# PH_074_isolated_SMD_rev1_2.net
KiCad netlist of a schematic drawn in EAGLE
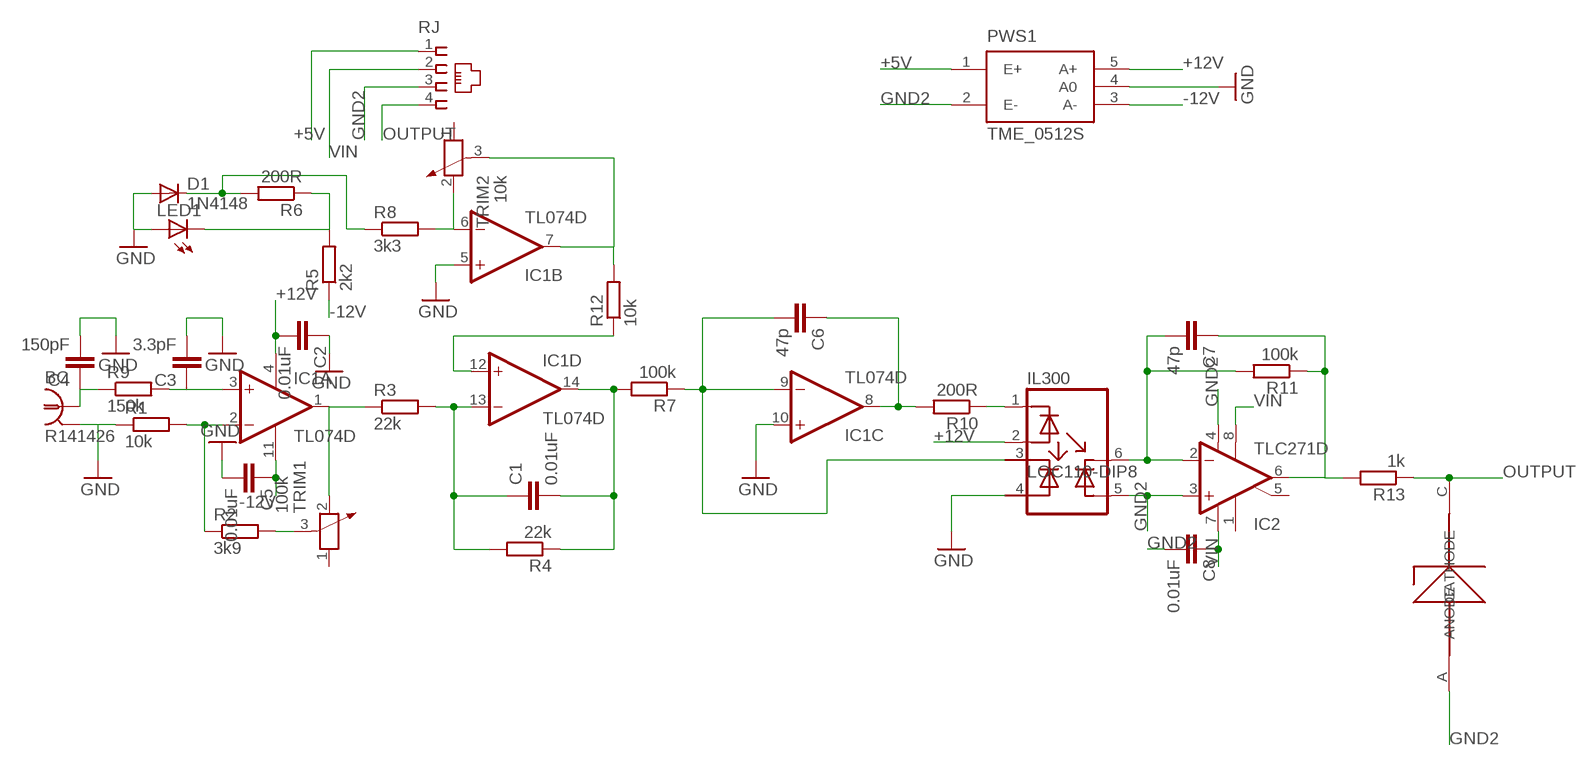
[diagram p0: schematic, sheet 1]

(export (version "E")
  (design (tool "Eeschema 10.0.6"))
  (components
    (comp (ref "BC")
      (value "R141426")
      (footprint "eagle-import:R141426")
      (fields (field (name "MF") "FARNELL") (field (name "MPN") "R141426161"))
      (libsource (lib "eagle-import") (part "R141426"))
    )
    (comp (ref "C1")
      (value "0.01uF")
      (footprint "eagle-import:C1206")
      (libsource (lib "eagle-import") (part "C-EUC1206"))
    )
    (comp (ref "C2")
      (value "0.01uF")
      (footprint "eagle-import:C1206")
      (libsource (lib "eagle-import") (part "C-EUC1206"))
    )
    (comp (ref "C3")
      (value "3.3pF")
      (footprint "eagle-import:C0805")
      (libsource (lib "eagle-import") (part "C-EUC0805"))
    )
    (comp (ref "C4")
      (value "150pF")
      (footprint "eagle-import:C0805")
      (libsource (lib "eagle-import") (part "C-EUC0805"))
    )
    (comp (ref "C5")
      (value "0.01uF")
      (footprint "eagle-import:C0805")
      (libsource (lib "eagle-import") (part "C-EUC0805"))
    )
    (comp (ref "C6")
      (value "47p")
      (footprint "eagle-import:C0805")
      (libsource (lib "eagle-import") (part "C-EUC0805"))
    )
    (comp (ref "C7")
      (value "47p")
      (footprint "eagle-import:C1206")
      (libsource (lib "eagle-import") (part "C-EUC1206"))
    )
    (comp (ref "C8")
      (value "0.01uF")
      (footprint "eagle-import:C0805")
      (libsource (lib "eagle-import") (part "C-EUC0805"))
    )
    (comp (ref "D1")
      (value "1N4148")
      (footprint "eagle-import:R1206W")
      (libsource (lib "eagle-import") (part "1N4148"))
    )
    (comp (ref "IC1")
      (value "TL074D")
      (footprint "eagle-import:SO14")
      (libsource (lib "eagle-import") (part "TL074D"))
    )
    (comp (ref "IC2")
      (value "TLC271D")
      (footprint "eagle-import:SO08")
      (libsource (lib "eagle-import") (part "TLC271D"))
    )
    (comp (ref "IL300")
      (value "LOC110-DIP8")
      (footprint "eagle-import:DIP8")
      (libsource (lib "eagle-import") (part "ILD621LOC110-DIP8"))
    )
    (comp (ref "LED1")
      (value "LED3MM")
      (footprint "eagle-import:LED3MM")
      (libsource (lib "eagle-import") (part "LED3MM"))
    )
    (comp (ref "PWS1")
      (value "TME_0512S")
      (footprint "eagle-import:TMEXXXXS")
      (fields (field (name "MPN") "TME 0512S"))
      (libsource (lib "eagle-import") (part "TME_S0512"))
    )
    (comp (ref "R1")
      (value "10k")
      (footprint "eagle-import:R1206W")
      (libsource (lib "eagle-import") (part "R-EU_R1206W"))
    )
    (comp (ref "R2")
      (value "3k9")
      (footprint "eagle-import:R1206W")
      (libsource (lib "eagle-import") (part "R-EU_R1206W"))
    )
    (comp (ref "R3")
      (value "22k")
      (footprint "eagle-import:R1206W")
      (libsource (lib "eagle-import") (part "R-EU_R1206W"))
    )
    (comp (ref "R4")
      (value "22k")
      (footprint "eagle-import:R1206W")
      (libsource (lib "eagle-import") (part "R-EU_R1206W"))
    )
    (comp (ref "R5")
      (value "2k2")
      (footprint "eagle-import:R1206W")
      (libsource (lib "eagle-import") (part "R-EU_R1206W"))
    )
    (comp (ref "R6")
      (value "200R")
      (footprint "eagle-import:R1206W")
      (libsource (lib "eagle-import") (part "R-EU_R1206W"))
    )
    (comp (ref "R7")
      (value "100k")
      (footprint "eagle-import:R1206W")
      (libsource (lib "eagle-import") (part "R-EU_R1206W"))
    )
    (comp (ref "R8")
      (value "3k3")
      (footprint "eagle-import:R1206W")
      (libsource (lib "eagle-import") (part "R-EU_R1206W"))
    )
    (comp (ref "R9")
      (value "150k")
      (footprint "eagle-import:R0805W")
      (libsource (lib "eagle-import") (part "R-EU_R0805W"))
    )
    (comp (ref "R10")
      (value "200R")
      (footprint "eagle-import:R1206W")
      (libsource (lib "eagle-import") (part "R-EU_R1206W"))
    )
    (comp (ref "R11")
      (value "100k")
      (footprint "eagle-import:R1206W")
      (libsource (lib "eagle-import") (part "R-EU_R1206W"))
    )
    (comp (ref "R12")
      (value "10k")
      (footprint "eagle-import:R1206W")
      (libsource (lib "eagle-import") (part "R-EU_R1206W"))
    )
    (comp (ref "R13")
      (value "1k")
      (footprint "eagle-import:R1206W")
      (libsource (lib "eagle-import") (part "R-EU_R1206W"))
    )
    (comp (ref "RJ")
      (value "14867")
      (footprint "eagle-import:14867")
      (libsource (lib "eagle-import") (part "14867"))
    )
    (comp (ref "TRIM1")
      (value "100k")
      (footprint "eagle-import:PT-10")
      (libsource (lib "eagle-import") (part "POTENTIOMETER_PT-10"))
    )
    (comp (ref "TRIM2")
      (value "10k")
      (footprint "eagle-import:PT-10")
      (libsource (lib "eagle-import") (part "POTENTIOMETER_PT-10"))
    )
    (comp (ref "U$1")
      (value "ZENER")
      (footprint "eagle-import:SOD80-W")
      (libsource (lib "eagle-import") (part "ZENER"))
    )
  )
  (nets
    (net (code "1") (name "/+5V") (class "Default")
      (node (ref "PWS1") (pin "1") (pinfunction "E+_1") (pintype "input"))
      (node (ref "RJ") (pin "1") (pinfunction "1_1") (pintype "passive"))
    )
    (net (code "2") (name "/+12V") (class "Default")
      (node (ref "C2") (pin "2") (pinfunction "2_2") (pintype "passive"))
      (node (ref "IC1") (pin "4") (pinfunction "V+_4") (pintype "power_in"))
      (node (ref "IL300") (pin "2") (pinfunction "2_2") (pintype "passive"))
      (node (ref "PWS1") (pin "5") (pinfunction "A+_5") (pintype "output"))
    )
    (net (code "3") (name "/-12V") (class "Default")
      (node (ref "C5") (pin "1") (pinfunction "1_1") (pintype "passive"))
      (node (ref "IC1") (pin "11") (pinfunction "V-_11") (pintype "power_in"))
      (node (ref "PWS1") (pin "3") (pinfunction "A-_3") (pintype "output"))
      (node (ref "R5") (pin "1") (pinfunction "1_1") (pintype "passive"))
    )
    (net (code "4") (name "/GND2") (class "Default")
      (node (ref "C8") (pin "2") (pinfunction "2_2") (pintype "passive"))
      (node (ref "IC2") (pin "3") (pinfunction "+IN_3") (pintype "input"))
      (node (ref "IC2") (pin "4") (pinfunction "V-_4") (pintype "power_in"))
      (node (ref "IL300") (pin "5") (pinfunction "5_5") (pintype "passive"))
      (node (ref "PWS1") (pin "2") (pinfunction "E-_2") (pintype "input"))
      (node (ref "RJ") (pin "3") (pinfunction "3_3") (pintype "passive"))
      (node (ref "U$1") (pin "A") (pinfunction "ANODE_A") (pintype "bidirectional"))
    )
    (net (code "5") (name "/OUTPUT") (class "Default")
      (node (ref "R13") (pin "1") (pinfunction "1_1") (pintype "passive"))
      (node (ref "RJ") (pin "4") (pinfunction "4_4") (pintype "passive"))
      (node (ref "U$1") (pin "C") (pinfunction "CATHODE_C") (pintype "bidirectional"))
    )
    (net (code "6") (name "/VIN") (class "Default")
      (node (ref "C8") (pin "1") (pinfunction "1_1") (pintype "passive"))
      (node (ref "IC2") (pin "7") (pinfunction "V+_7") (pintype "power_in"))
      (node (ref "IC2") (pin "8") (pinfunction "OPT_8") (pintype "passive"))
      (node (ref "RJ") (pin "2") (pinfunction "2_2") (pintype "passive"))
    )
    (net (code "7") (name "GND") (class "Default")
      (node (ref "BC") (pin "2") (pinfunction "GND_2") (pintype "power_in"))
      (node (ref "C2") (pin "1") (pinfunction "1_1") (pintype "passive"))
      (node (ref "C3") (pin "2") (pinfunction "2_2") (pintype "passive"))
      (node (ref "C4") (pin "2") (pinfunction "2_2") (pintype "passive"))
      (node (ref "C5") (pin "2") (pinfunction "2_2") (pintype "passive"))
      (node (ref "D1") (pin "1") (pinfunction "A_1") (pintype "passive"))
      (node (ref "IC1") (pin "10") (pinfunction "+IN_10") (pintype "input"))
      (node (ref "IC1") (pin "5") (pinfunction "+IN_5") (pintype "input"))
      (node (ref "IL300") (pin "4") (pinfunction "4_4") (pintype "passive"))
      (node (ref "LED1") (pin "A") (pinfunction "A_A") (pintype "passive"))
      (node (ref "PWS1") (pin "4") (pinfunction "A0_4") (pintype "output"))
      (node (ref "R1") (pin "1") (pinfunction "1_1") (pintype "passive"))
    )
    (net (code "8") (name "Net-(BC-Pad1)") (class "Default")
      (node (ref "BC") (pin "1") (pinfunction "1_1") (pintype "passive"))
      (node (ref "C4") (pin "1") (pinfunction "1_1") (pintype "passive"))
      (node (ref "R9") (pin "1") (pinfunction "1_1") (pintype "passive"))
    )
    (net (code "9") (name "Net-(D1-C)") (class "Default")
      (node (ref "D1") (pin "2") (pinfunction "C_2") (pintype "passive"))
      (node (ref "R6") (pin "2") (pinfunction "2_2") (pintype "passive"))
      (node (ref "R8") (pin "1") (pinfunction "1_1") (pintype "passive"))
    )
    (net (code "10") (name "Net-(IC1A-+IN)") (class "Default")
      (node (ref "C3") (pin "1") (pinfunction "1_1") (pintype "passive"))
      (node (ref "IC1") (pin "3") (pinfunction "+IN_3") (pintype "input"))
      (node (ref "R9") (pin "2") (pinfunction "2_2") (pintype "passive"))
    )
    (net (code "11") (name "Net-(IC1A--IN)") (class "Default")
      (node (ref "IC1") (pin "2") (pinfunction "-IN_2") (pintype "input"))
      (node (ref "R1") (pin "2") (pinfunction "2_2") (pintype "passive"))
      (node (ref "R2") (pin "1") (pinfunction "1_1") (pintype "passive"))
    )
    (net (code "12") (name "Net-(IC1A-OUT)") (class "Default")
      (node (ref "IC1") (pin "1") (pinfunction "OUT_1") (pintype "output"))
      (node (ref "R3") (pin "1") (pinfunction "1_1") (pintype "passive"))
      (node (ref "TRIM1") (pin "2") (pinfunction "2_2") (pintype "passive"))
    )
    (net (code "13") (name "Net-(IC1B--IN)") (class "Default")
      (node (ref "IC1") (pin "6") (pinfunction "-IN_6") (pintype "input"))
      (node (ref "R8") (pin "2") (pinfunction "2_2") (pintype "passive"))
      (node (ref "TRIM2") (pin "2") (pinfunction "2_2") (pintype "passive"))
    )
    (net (code "14") (name "Net-(IC1B-OUT)") (class "Default")
      (node (ref "IC1") (pin "7") (pinfunction "OUT_7") (pintype "output"))
      (node (ref "R12") (pin "2") (pinfunction "2_2") (pintype "passive"))
      (node (ref "TRIM2") (pin "3") (pinfunction "3_3") (pintype "passive"))
    )
    (net (code "15") (name "Net-(IC1C--IN)") (class "Default")
      (node (ref "C6") (pin "2") (pinfunction "2_2") (pintype "passive"))
      (node (ref "IC1") (pin "9") (pinfunction "-IN_9") (pintype "input"))
      (node (ref "IL300") (pin "3") (pinfunction "3_3") (pintype "passive"))
      (node (ref "R7") (pin "1") (pinfunction "1_1") (pintype "passive"))
    )
    (net (code "16") (name "Net-(IC1C-OUT)") (class "Default")
      (node (ref "C6") (pin "1") (pinfunction "1_1") (pintype "passive"))
      (node (ref "IC1") (pin "8") (pinfunction "OUT_8") (pintype "output"))
      (node (ref "R10") (pin "2") (pinfunction "2_2") (pintype "passive"))
    )
    (net (code "17") (name "Net-(IC1D-+IN)") (class "Default")
      (node (ref "IC1") (pin "12") (pinfunction "+IN_12") (pintype "input"))
      (node (ref "R12") (pin "1") (pinfunction "1_1") (pintype "passive"))
    )
    (net (code "18") (name "Net-(IC1D--IN)") (class "Default")
      (node (ref "C1") (pin "1") (pinfunction "1_1") (pintype "passive"))
      (node (ref "IC1") (pin "13") (pinfunction "-IN_13") (pintype "input"))
      (node (ref "R3") (pin "2") (pinfunction "2_2") (pintype "passive"))
      (node (ref "R4") (pin "2") (pinfunction "2_2") (pintype "passive"))
    )
    (net (code "19") (name "Net-(IC1D-OUT)") (class "Default")
      (node (ref "C1") (pin "2") (pinfunction "2_2") (pintype "passive"))
      (node (ref "IC1") (pin "14") (pinfunction "OUT_14") (pintype "output"))
      (node (ref "R4") (pin "1") (pinfunction "1_1") (pintype "passive"))
      (node (ref "R7") (pin "2") (pinfunction "2_2") (pintype "passive"))
    )
    (net (code "20") (name "Net-(IC2--IN)") (class "Default")
      (node (ref "C7") (pin "2") (pinfunction "2_2") (pintype "passive"))
      (node (ref "IC2") (pin "2") (pinfunction "-IN_2") (pintype "input"))
      (node (ref "IL300") (pin "6") (pinfunction "6_6") (pintype "passive"))
      (node (ref "R11") (pin "2") (pinfunction "2_2") (pintype "passive"))
    )
    (net (code "21") (name "Net-(IC2-OUT)") (class "Default")
      (node (ref "C7") (pin "1") (pinfunction "1_1") (pintype "passive"))
      (node (ref "IC2") (pin "6") (pinfunction "OUT_6") (pintype "output"))
      (node (ref "R11") (pin "1") (pinfunction "1_1") (pintype "passive"))
      (node (ref "R13") (pin "2") (pinfunction "2_2") (pintype "passive"))
    )
    (net (code "22") (name "Net-(IL300-Pad1)") (class "Default")
      (node (ref "IL300") (pin "1") (pinfunction "1_1") (pintype "passive"))
      (node (ref "R10") (pin "1") (pinfunction "1_1") (pintype "passive"))
    )
    (net (code "23") (name "Net-(LED1-C)") (class "Default")
      (node (ref "LED1") (pin "K") (pinfunction "C_K") (pintype "passive"))
      (node (ref "R5") (pin "2") (pinfunction "2_2") (pintype "passive"))
      (node (ref "R6") (pin "1") (pinfunction "1_1") (pintype "passive"))
    )
    (net (code "24") (name "Net-(R2-Pad2)") (class "Default")
      (node (ref "R2") (pin "2") (pinfunction "2_2") (pintype "passive"))
      (node (ref "TRIM1") (pin "3") (pinfunction "3_3") (pintype "passive"))
    )
    (net (code "25") (name "unconnected-(IC2-ON1-Pad1)") (class "Default")
      (node (ref "IC2") (pin "1") (pinfunction "ON1_1") (pintype "passive"))
    )
    (net (code "26") (name "unconnected-(IC2-ON2-Pad5)") (class "Default")
      (node (ref "IC2") (pin "5") (pinfunction "ON2_5") (pintype "passive"))
    )
    (net (code "27") (name "unconnected-(TRIM1-Pad1)") (class "Default")
      (node (ref "TRIM1") (pin "1") (pinfunction "1_1") (pintype "passive"))
    )
    (net (code "28") (name "unconnected-(TRIM2-Pad1)") (class "Default")
      (node (ref "TRIM2") (pin "1") (pinfunction "1_1") (pintype "passive"))
    )
  )
)
